# Input_chanel.net
KiCad netlist of a schematic drawn in Altium Designer
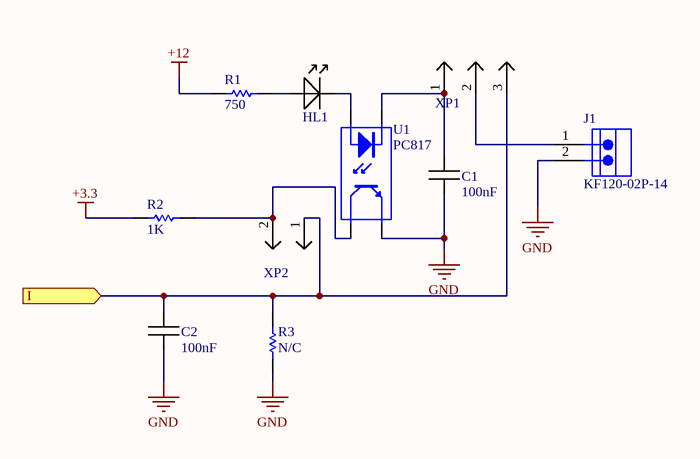
[diagram p0: Input_chanel.SchDoc]

(export (version "E")
  (design (tool "Eeschema 10.0.6"))
  (components
    (comp (ref "C1")
      (value "CAP_SMD")
      (footprint "CAP0805")
      (description "Ceramic capacitor, 0805")
      (fields (field (name "VAL") "100nF"))
      (libsource (lib "altium-import") (part "root_1_CAP_SMD_"))
    )
    (comp (ref "C2")
      (value "CAP_SMD")
      (footprint "CAP0805")
      (description "Ceramic capacitor, 0805")
      (fields (field (name "VAL") "100nF"))
      (libsource (lib "altium-import") (part "root_1_CAP_SMD_"))
    )
    (comp (ref "HL1")
      (value "LED_SMD")
      (footprint "0805_LED")
      (description "0805 led")
      (libsource (lib "altium-import") (part "root_0_LED_SMD_"))
    )
    (comp (ref "J1")
      (value "KF120-02P-14")
      (footprint "KF350-3.5-02P")
      (fields (field (name "MANUFACTURER") "Cixi KaiFeng") (field (name "CONTACT") "Brass"))
      (libsource (lib "altium-import") (part "root_3_Terminal_2_"))
    )
    (comp (ref "R1")
      (value "RES_SMD")
      (footprint "RES0805")
      (fields (field (name "VAL") "750"))
      (libsource (lib "altium-import") (part "root_0_RES_SMD_"))
    )
    (comp (ref "R2")
      (value "RES_SMD")
      (footprint "RES0805")
      (fields (field (name "VAL") "1K"))
      (libsource (lib "altium-import") (part "root_0_RES_SMD_"))
    )
    (comp (ref "R3")
      (value "RES_SMD")
      (footprint "RES0805")
      (fields (field (name "VAL") "N/C"))
      (libsource (lib "altium-import") (part "root_1_RES_SMD_"))
    )
    (comp (ref "U1")
      (value "PC817")
      (footprint "DIP-4 - SMT")
      (description "4-Pin Phototransistor Optocoupler")
      (fields (field (name "PUBLISHER") "Altium Limited"))
      (libsource (lib "altium-import") (part "root_3_mirrored_PC817_"))
    )
    (comp (ref "XP1")
      (value "PLS-03")
      (footprint "PLS-03")
      (libsource (lib "altium-import") (part "root_1_PLS-03_"))
    )
    (comp (ref "XP2")
      (value "PLS-02")
      (footprint "PLS-02")
      (libsource (lib "altium-import") (part "root_3_PLS-02_"))
    )
  )
  (nets
    (net (code "1") (name "+3.3") (class "Default")
      (node (ref "R2") (pin "1") (pinfunction "1_1") (pintype "passive"))
    )
    (net (code "2") (name "+12") (class "Default")
      (node (ref "R1") (pin "1") (pinfunction "1_1") (pintype "passive"))
    )
    (net (code "3") (name "/I") (class "Default")
      (node (ref "C2") (pin "2") (pinfunction "2_2") (pintype "passive"))
      (node (ref "R3") (pin "2") (pinfunction "2_2") (pintype "passive"))
      (node (ref "XP1") (pin "3") (pinfunction "3_3") (pintype "passive"))
      (node (ref "XP2") (pin "1") (pinfunction "1_1") (pintype "passive"))
    )
    (net (code "4") (name "GND") (class "Default")
      (node (ref "C1") (pin "1") (pinfunction "1_1") (pintype "passive"))
      (node (ref "C2") (pin "1") (pinfunction "1_1") (pintype "passive"))
      (node (ref "J1") (pin "2") (pinfunction "2_2") (pintype "passive"))
      (node (ref "R3") (pin "1") (pinfunction "1_1") (pintype "passive"))
      (node (ref "U1") (pin "3") (pinfunction "E_3") (pintype "passive"))
    )
    (net (code "5") (name "Net-(HL1-anode)") (class "Default")
      (node (ref "HL1") (pin "1") (pinfunction "anode_1") (pintype "passive"))
      (node (ref "R1") (pin "2") (pinfunction "2_2") (pintype "passive"))
    )
    (net (code "6") (name "Net-(HL1-cathode)") (class "Default")
      (node (ref "HL1") (pin "2") (pinfunction "cathode_2") (pintype "passive"))
      (node (ref "U1") (pin "1") (pinfunction "A_1") (pintype "passive"))
    )
    (net (code "7") (name "Net-(J1-Pad1)") (class "Default")
      (node (ref "J1") (pin "1") (pinfunction "1_1") (pintype "passive"))
      (node (ref "XP1") (pin "2") (pinfunction "2_2") (pintype "passive"))
    )
    (net (code "8") (name "Net-(U1-C)") (class "Default")
      (node (ref "R2") (pin "2") (pinfunction "2_2") (pintype "passive"))
      (node (ref "U1") (pin "4") (pinfunction "C_4") (pintype "passive"))
      (node (ref "XP2") (pin "2") (pinfunction "2_2") (pintype "passive"))
    )
    (net (code "9") (name "Net-(U1-K)") (class "Default")
      (node (ref "C1") (pin "2") (pinfunction "2_2") (pintype "passive"))
      (node (ref "U1") (pin "2") (pinfunction "K_2") (pintype "passive"))
      (node (ref "XP1") (pin "1") (pinfunction "1_1") (pintype "passive"))
    )
  )
)
